# MB1115.net
KiCad netlist of a schematic drawn in Altium Designer
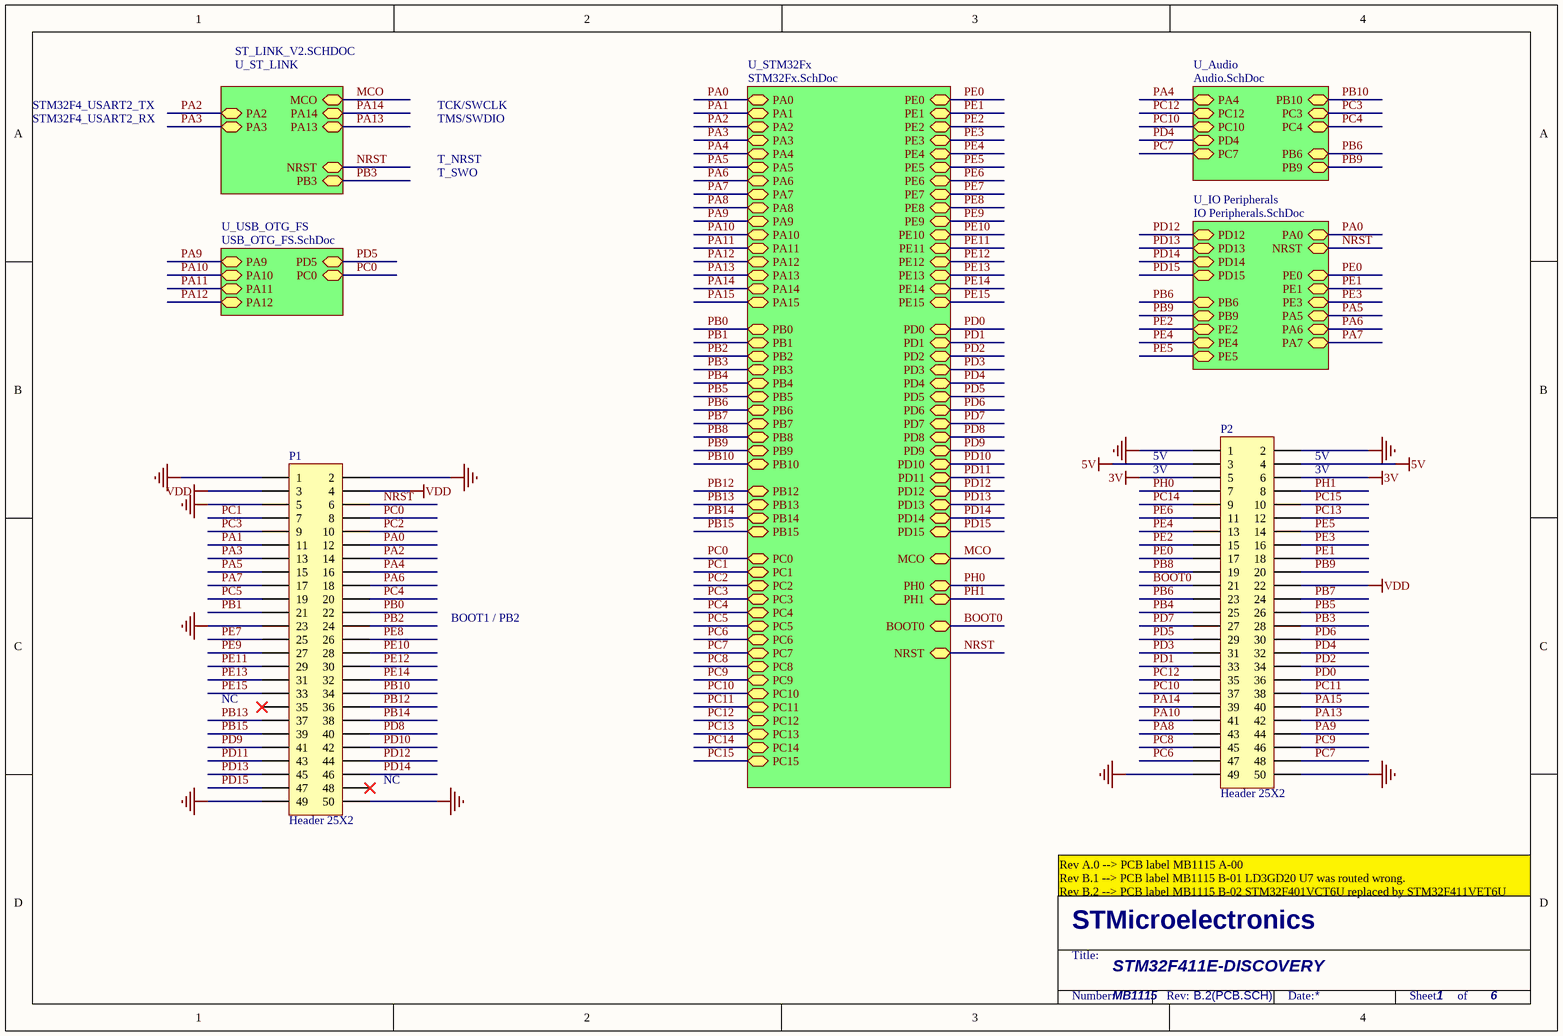
[diagram p0: MB1115.SchDoc]

(export (version "E")
  (design (tool "Eeschema 10.0.6"))
  (components
    (comp (ref "P1")
      (value "Header 25X2")
      (footprint "HDR2X25")
      (description "Header, 25-Pin, Dual row")
      (fields (field (name "PUBLISHER") "Altium Limited"))
      (libsource (lib "Miscellaneous Connectors") (part "Header 25X2"))
    )
    (comp (ref "P2")
      (value "Header 25X2")
      (footprint "HDR2X25")
      (description "Header, 25-Pin, Dual row")
      (fields (field (name "PUBLISHER") "Altium Limited"))
      (libsource (lib "Miscellaneous Connectors") (part "Header 25X2"))
    )
  )
  (nets
    (net (code "1") (name "/BOOT0") (class "Default")
      (node (ref "P2") (pin "21") (pinfunction "21_21") (pintype "passive"))
    )
    (net (code "3") (name "/NRST") (class "Default")
      (node (ref "P1") (pin "6") (pinfunction "6_6") (pintype "passive"))
    )
    (net (code "4") (name "/PA0") (class "Default")
      (node (ref "P1") (pin "12") (pinfunction "12_12") (pintype "passive"))
    )
    (net (code "5") (name "/PA1") (class "Default")
      (node (ref "P1") (pin "11") (pinfunction "11_11") (pintype "passive"))
    )
    (net (code "6") (name "/PA2") (class "Default")
      (node (ref "P1") (pin "14") (pinfunction "14_14") (pintype "passive"))
    )
    (net (code "7") (name "/PA3") (class "Default")
      (node (ref "P1") (pin "13") (pinfunction "13_13") (pintype "passive"))
    )
    (net (code "8") (name "/PA4") (class "Default")
      (node (ref "P1") (pin "16") (pinfunction "16_16") (pintype "passive"))
    )
    (net (code "9") (name "/PA5") (class "Default")
      (node (ref "P1") (pin "15") (pinfunction "15_15") (pintype "passive"))
    )
    (net (code "10") (name "/PA6") (class "Default")
      (node (ref "P1") (pin "18") (pinfunction "18_18") (pintype "passive"))
    )
    (net (code "11") (name "/PA7") (class "Default")
      (node (ref "P1") (pin "17") (pinfunction "17_17") (pintype "passive"))
    )
    (net (code "12") (name "/PA8") (class "Default")
      (node (ref "P2") (pin "43") (pinfunction "43_43") (pintype "passive"))
    )
    (net (code "13") (name "/PA9") (class "Default")
      (node (ref "P2") (pin "44") (pinfunction "44_44") (pintype "passive"))
    )
    (net (code "14") (name "/PA10") (class "Default")
      (node (ref "P2") (pin "41") (pinfunction "41_41") (pintype "passive"))
    )
    (net (code "17") (name "/PA13") (class "Default")
      (node (ref "P2") (pin "42") (pinfunction "42_42") (pintype "passive"))
    )
    (net (code "18") (name "/PA14") (class "Default")
      (node (ref "P2") (pin "39") (pinfunction "39_39") (pintype "passive"))
    )
    (net (code "19") (name "/PA15") (class "Default")
      (node (ref "P2") (pin "40") (pinfunction "40_40") (pintype "passive"))
    )
    (net (code "20") (name "/PB0") (class "Default")
      (node (ref "P1") (pin "22") (pinfunction "22_22") (pintype "passive"))
    )
    (net (code "21") (name "/PB1") (class "Default")
      (node (ref "P1") (pin "21") (pinfunction "21_21") (pintype "passive"))
    )
    (net (code "22") (name "/PB2") (class "Default")
      (node (ref "P1") (pin "24") (pinfunction "24_24") (pintype "passive"))
    )
    (net (code "23") (name "/PB3") (class "Default")
      (node (ref "P2") (pin "28") (pinfunction "28_28") (pintype "passive"))
    )
    (net (code "24") (name "/PB4") (class "Default")
      (node (ref "P2") (pin "25") (pinfunction "25_25") (pintype "passive"))
    )
    (net (code "25") (name "/PB5") (class "Default")
      (node (ref "P2") (pin "26") (pinfunction "26_26") (pintype "passive"))
    )
    (net (code "26") (name "/PB6") (class "Default")
      (node (ref "P2") (pin "23") (pinfunction "23_23") (pintype "passive"))
    )
    (net (code "27") (name "/PB7") (class "Default")
      (node (ref "P2") (pin "24") (pinfunction "24_24") (pintype "passive"))
    )
    (net (code "28") (name "/PB8") (class "Default")
      (node (ref "P2") (pin "19") (pinfunction "19_19") (pintype "passive"))
    )
    (net (code "29") (name "/PB9") (class "Default")
      (node (ref "P2") (pin "20") (pinfunction "20_20") (pintype "passive"))
    )
    (net (code "30") (name "/PB10") (class "Default")
      (node (ref "P1") (pin "34") (pinfunction "34_34") (pintype "passive"))
    )
    (net (code "31") (name "/PB12") (class "Default")
      (node (ref "P1") (pin "36") (pinfunction "36_36") (pintype "passive"))
    )
    (net (code "32") (name "/PB13") (class "Default")
      (node (ref "P1") (pin "37") (pinfunction "37_37") (pintype "passive"))
    )
    (net (code "33") (name "/PB14") (class "Default")
      (node (ref "P1") (pin "38") (pinfunction "38_38") (pintype "passive"))
    )
    (net (code "34") (name "/PB15") (class "Default")
      (node (ref "P1") (pin "39") (pinfunction "39_39") (pintype "passive"))
    )
    (net (code "35") (name "/PC0") (class "Default")
      (node (ref "P1") (pin "8") (pinfunction "8_8") (pintype "passive"))
    )
    (net (code "36") (name "/PC1") (class "Default")
      (node (ref "P1") (pin "7") (pinfunction "7_7") (pintype "passive"))
    )
    (net (code "37") (name "/PC2") (class "Default")
      (node (ref "P1") (pin "10") (pinfunction "10_10") (pintype "passive"))
    )
    (net (code "38") (name "/PC3") (class "Default")
      (node (ref "P1") (pin "9") (pinfunction "9_9") (pintype "passive"))
    )
    (net (code "39") (name "/PC4") (class "Default")
      (node (ref "P1") (pin "20") (pinfunction "20_20") (pintype "passive"))
    )
    (net (code "40") (name "/PC5") (class "Default")
      (node (ref "P1") (pin "19") (pinfunction "19_19") (pintype "passive"))
    )
    (net (code "41") (name "/PC6") (class "Default")
      (node (ref "P2") (pin "47") (pinfunction "47_47") (pintype "passive"))
    )
    (net (code "42") (name "/PC7") (class "Default")
      (node (ref "P2") (pin "48") (pinfunction "48_48") (pintype "passive"))
    )
    (net (code "43") (name "/PC8") (class "Default")
      (node (ref "P2") (pin "45") (pinfunction "45_45") (pintype "passive"))
    )
    (net (code "44") (name "/PC9") (class "Default")
      (node (ref "P2") (pin "46") (pinfunction "46_46") (pintype "passive"))
    )
    (net (code "45") (name "/PC10") (class "Default")
      (node (ref "P2") (pin "37") (pinfunction "37_37") (pintype "passive"))
    )
    (net (code "46") (name "/PC11") (class "Default")
      (node (ref "P2") (pin "38") (pinfunction "38_38") (pintype "passive"))
    )
    (net (code "47") (name "/PC12") (class "Default")
      (node (ref "P2") (pin "35") (pinfunction "35_35") (pintype "passive"))
    )
    (net (code "48") (name "/PC13") (class "Default")
      (node (ref "P2") (pin "12") (pinfunction "12_12") (pintype "passive"))
    )
    (net (code "49") (name "/PC14") (class "Default")
      (node (ref "P2") (pin "9") (pinfunction "9_9") (pintype "passive"))
    )
    (net (code "50") (name "/PC15") (class "Default")
      (node (ref "P2") (pin "10") (pinfunction "10_10") (pintype "passive"))
    )
    (net (code "51") (name "/PD0") (class "Default")
      (node (ref "P2") (pin "36") (pinfunction "36_36") (pintype "passive"))
    )
    (net (code "52") (name "/PD1") (class "Default")
      (node (ref "P2") (pin "33") (pinfunction "33_33") (pintype "passive"))
    )
    (net (code "53") (name "/PD2") (class "Default")
      (node (ref "P2") (pin "34") (pinfunction "34_34") (pintype "passive"))
    )
    (net (code "54") (name "/PD3") (class "Default")
      (node (ref "P2") (pin "31") (pinfunction "31_31") (pintype "passive"))
    )
    (net (code "55") (name "/PD4") (class "Default")
      (node (ref "P2") (pin "32") (pinfunction "32_32") (pintype "passive"))
    )
    (net (code "56") (name "/PD5") (class "Default")
      (node (ref "P2") (pin "29") (pinfunction "29_29") (pintype "passive"))
    )
    (net (code "57") (name "/PD6") (class "Default")
      (node (ref "P2") (pin "30") (pinfunction "30_30") (pintype "passive"))
    )
    (net (code "58") (name "/PD7") (class "Default")
      (node (ref "P2") (pin "27") (pinfunction "27_27") (pintype "passive"))
    )
    (net (code "59") (name "/PD8") (class "Default")
      (node (ref "P1") (pin "40") (pinfunction "40_40") (pintype "passive"))
    )
    (net (code "60") (name "/PD9") (class "Default")
      (node (ref "P1") (pin "41") (pinfunction "41_41") (pintype "passive"))
    )
    (net (code "61") (name "/PD10") (class "Default")
      (node (ref "P1") (pin "42") (pinfunction "42_42") (pintype "passive"))
    )
    (net (code "62") (name "/PD11") (class "Default")
      (node (ref "P1") (pin "43") (pinfunction "43_43") (pintype "passive"))
    )
    (net (code "63") (name "/PD12") (class "Default")
      (node (ref "P1") (pin "44") (pinfunction "44_44") (pintype "passive"))
    )
    (net (code "64") (name "/PD13") (class "Default")
      (node (ref "P1") (pin "45") (pinfunction "45_45") (pintype "passive"))
    )
    (net (code "65") (name "/PD14") (class "Default")
      (node (ref "P1") (pin "46") (pinfunction "46_46") (pintype "passive"))
    )
    (net (code "66") (name "/PD15") (class "Default")
      (node (ref "P1") (pin "47") (pinfunction "47_47") (pintype "passive"))
    )
    (net (code "67") (name "/PE0") (class "Default")
      (node (ref "P2") (pin "17") (pinfunction "17_17") (pintype "passive"))
    )
    (net (code "68") (name "/PE1") (class "Default")
      (node (ref "P2") (pin "18") (pinfunction "18_18") (pintype "passive"))
    )
    (net (code "69") (name "/PE2") (class "Default")
      (node (ref "P2") (pin "15") (pinfunction "15_15") (pintype "passive"))
    )
    (net (code "70") (name "/PE3") (class "Default")
      (node (ref "P2") (pin "16") (pinfunction "16_16") (pintype "passive"))
    )
    (net (code "71") (name "/PE4") (class "Default")
      (node (ref "P2") (pin "13") (pinfunction "13_13") (pintype "passive"))
    )
    (net (code "72") (name "/PE5") (class "Default")
      (node (ref "P2") (pin "14") (pinfunction "14_14") (pintype "passive"))
    )
    (net (code "73") (name "/PE6") (class "Default")
      (node (ref "P2") (pin "11") (pinfunction "11_11") (pintype "passive"))
    )
    (net (code "74") (name "/PE7") (class "Default")
      (node (ref "P1") (pin "25") (pinfunction "25_25") (pintype "passive"))
    )
    (net (code "75") (name "/PE8") (class "Default")
      (node (ref "P1") (pin "26") (pinfunction "26_26") (pintype "passive"))
    )
    (net (code "76") (name "/PE9") (class "Default")
      (node (ref "P1") (pin "27") (pinfunction "27_27") (pintype "passive"))
    )
    (net (code "77") (name "/PE10") (class "Default")
      (node (ref "P1") (pin "28") (pinfunction "28_28") (pintype "passive"))
    )
    (net (code "78") (name "/PE11") (class "Default")
      (node (ref "P1") (pin "29") (pinfunction "29_29") (pintype "passive"))
    )
    (net (code "79") (name "/PE12") (class "Default")
      (node (ref "P1") (pin "30") (pinfunction "30_30") (pintype "passive"))
    )
    (net (code "80") (name "/PE13") (class "Default")
      (node (ref "P1") (pin "31") (pinfunction "31_31") (pintype "passive"))
    )
    (net (code "81") (name "/PE14") (class "Default")
      (node (ref "P1") (pin "32") (pinfunction "32_32") (pintype "passive"))
    )
    (net (code "82") (name "/PE15") (class "Default")
      (node (ref "P1") (pin "33") (pinfunction "33_33") (pintype "passive"))
    )
    (net (code "83") (name "/PH0") (class "Default")
      (node (ref "P2") (pin "7") (pinfunction "7_7") (pintype "passive"))
    )
    (net (code "84") (name "/PH1") (class "Default")
      (node (ref "P2") (pin "8") (pinfunction "8_8") (pintype "passive"))
    )
    (net (code "85") (name "3V") (class "Default")
      (node (ref "P2") (pin "5") (pinfunction "5_5") (pintype "passive"))
      (node (ref "P2") (pin "6") (pinfunction "6_6") (pintype "passive"))
    )
    (net (code "86") (name "5V") (class "Default")
      (node (ref "P2") (pin "3") (pinfunction "3_3") (pintype "passive"))
      (node (ref "P2") (pin "4") (pinfunction "4_4") (pintype "passive"))
    )
    (net (code "87") (name "GND") (class "Default")
      (node (ref "P1") (pin "1") (pinfunction "1_1") (pintype "passive"))
      (node (ref "P1") (pin "2") (pinfunction "2_2") (pintype "passive"))
      (node (ref "P1") (pin "23") (pinfunction "23_23") (pintype "passive"))
      (node (ref "P1") (pin "49") (pinfunction "49_49") (pintype "passive"))
      (node (ref "P1") (pin "5") (pinfunction "5_5") (pintype "passive"))
      (node (ref "P1") (pin "50") (pinfunction "50_50") (pintype "passive"))
      (node (ref "P2") (pin "1") (pinfunction "1_1") (pintype "passive"))
      (node (ref "P2") (pin "2") (pinfunction "2_2") (pintype "passive"))
      (node (ref "P2") (pin "49") (pinfunction "49_49") (pintype "passive"))
      (node (ref "P2") (pin "50") (pinfunction "50_50") (pintype "passive"))
    )
    (net (code "88") (name "VDD") (class "Default")
      (node (ref "P1") (pin "3") (pinfunction "3_3") (pintype "passive"))
      (node (ref "P1") (pin "4") (pinfunction "4_4") (pintype "passive"))
      (node (ref "P2") (pin "22") (pinfunction "22_22") (pintype "passive"))
    )
    (net (code "89") (name "unconnected-(P1-Pad35)") (class "Default")
      (node (ref "P1") (pin "35") (pinfunction "35_35") (pintype "passive+no_connect"))
    )
    (net (code "90") (name "unconnected-(P1-Pad48)") (class "Default")
      (node (ref "P1") (pin "48") (pinfunction "48_48") (pintype "passive+no_connect"))
    )
  )
)
